# M228X.net
KiCad netlist of a schematic drawn in EAGLE
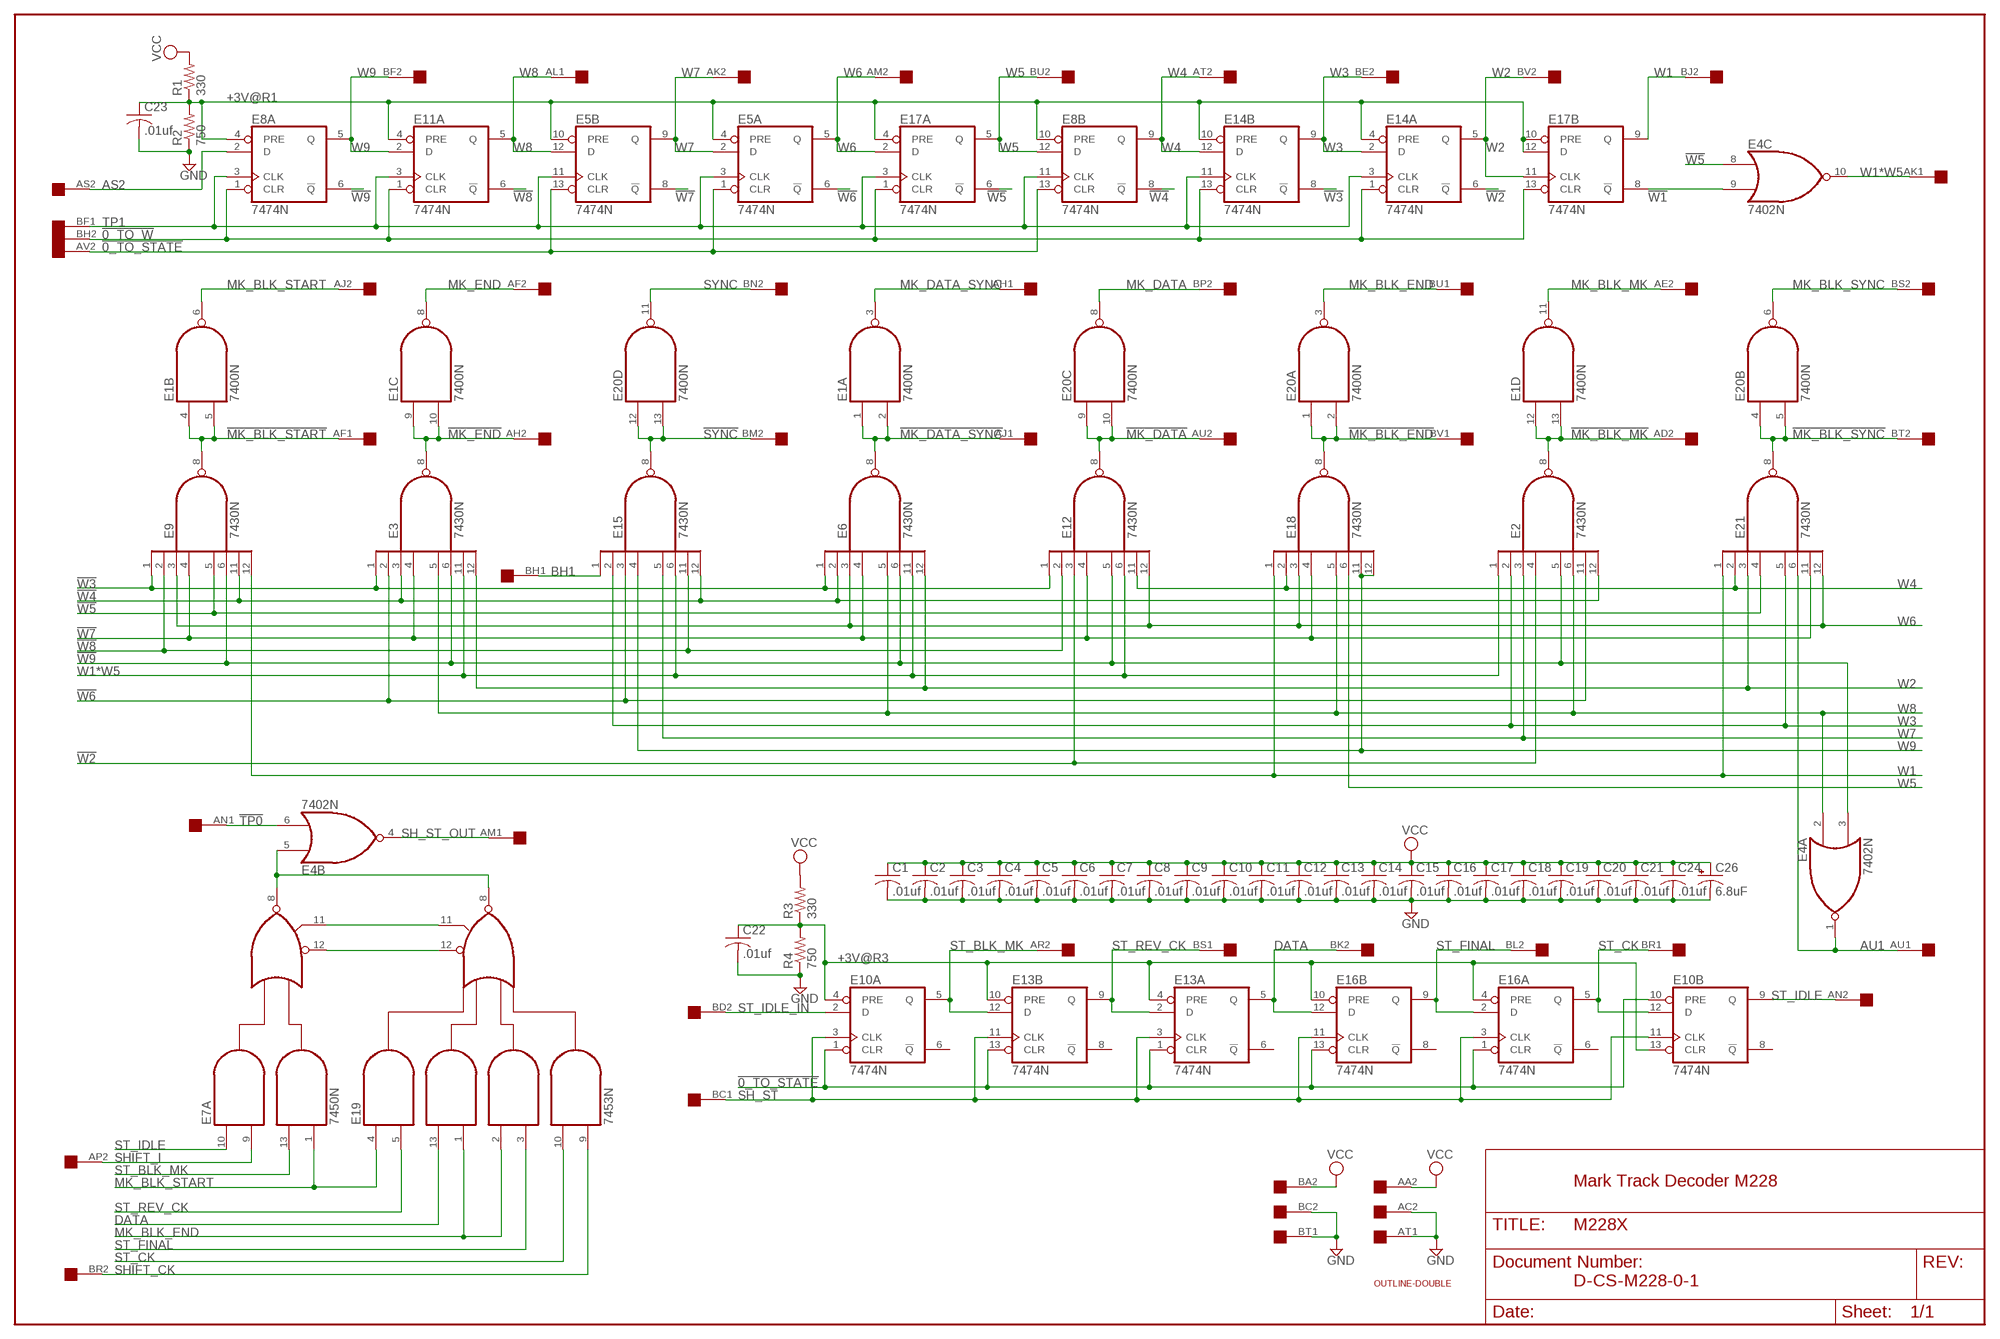
[diagram p0: schematic, sheet 1]

(export (version "E")
  (design (tool "Eeschema 10.0.6"))
  (components
    (comp (ref "C1")
      (value ".01uf")
      (footprint "eagle-import:C050-025X075")
      (libsource (lib "eagle-import") (part "C-US050-025X075"))
    )
    (comp (ref "C2")
      (value ".01uf")
      (footprint "eagle-import:C050-025X075")
      (libsource (lib "eagle-import") (part "C-US050-025X075"))
    )
    (comp (ref "C3")
      (value ".01uf")
      (footprint "eagle-import:C050-025X075")
      (libsource (lib "eagle-import") (part "C-US050-025X075"))
    )
    (comp (ref "C4")
      (value ".01uf")
      (footprint "eagle-import:C050-025X075")
      (libsource (lib "eagle-import") (part "C-US050-025X075"))
    )
    (comp (ref "C5")
      (value ".01uf")
      (footprint "eagle-import:C050-025X075")
      (libsource (lib "eagle-import") (part "C-US050-025X075"))
    )
    (comp (ref "C6")
      (value ".01uf")
      (footprint "eagle-import:C050-025X075")
      (libsource (lib "eagle-import") (part "C-US050-025X075"))
    )
    (comp (ref "C7")
      (value ".01uf")
      (footprint "eagle-import:C050-025X075")
      (libsource (lib "eagle-import") (part "C-US050-025X075"))
    )
    (comp (ref "C8")
      (value ".01uf")
      (footprint "eagle-import:C050-025X075")
      (libsource (lib "eagle-import") (part "C-US050-025X075"))
    )
    (comp (ref "C9")
      (value ".01uf")
      (footprint "eagle-import:C050-025X075")
      (libsource (lib "eagle-import") (part "C-US050-025X075"))
    )
    (comp (ref "C10")
      (value ".01uf")
      (footprint "eagle-import:C050-025X075")
      (libsource (lib "eagle-import") (part "C-US050-025X075"))
    )
    (comp (ref "C11")
      (value ".01uf")
      (footprint "eagle-import:C050-025X075")
      (libsource (lib "eagle-import") (part "C-US050-025X075"))
    )
    (comp (ref "C12")
      (value ".01uf")
      (footprint "eagle-import:C050-025X075")
      (libsource (lib "eagle-import") (part "C-US050-025X075"))
    )
    (comp (ref "C13")
      (value ".01uf")
      (footprint "eagle-import:C050-025X075")
      (libsource (lib "eagle-import") (part "C-US050-025X075"))
    )
    (comp (ref "C14")
      (value ".01uf")
      (footprint "eagle-import:C050-025X075")
      (libsource (lib "eagle-import") (part "C-US050-025X075"))
    )
    (comp (ref "C15")
      (value ".01uf")
      (footprint "eagle-import:C050-025X075")
      (libsource (lib "eagle-import") (part "C-US050-025X075"))
    )
    (comp (ref "C16")
      (value ".01uf")
      (footprint "eagle-import:C050-025X075")
      (libsource (lib "eagle-import") (part "C-US050-025X075"))
    )
    (comp (ref "C17")
      (value ".01uf")
      (footprint "eagle-import:C050-025X075")
      (libsource (lib "eagle-import") (part "C-US050-025X075"))
    )
    (comp (ref "C18")
      (value ".01uf")
      (footprint "eagle-import:C050-025X075")
      (libsource (lib "eagle-import") (part "C-US050-025X075"))
    )
    (comp (ref "C19")
      (value ".01uf")
      (footprint "eagle-import:C050-025X075")
      (libsource (lib "eagle-import") (part "C-US050-025X075"))
    )
    (comp (ref "C20")
      (value ".01uf")
      (footprint "eagle-import:C050-025X075")
      (libsource (lib "eagle-import") (part "C-US050-025X075"))
    )
    (comp (ref "C21")
      (value ".01uf")
      (footprint "eagle-import:C050-025X075")
      (libsource (lib "eagle-import") (part "C-US050-025X075"))
    )
    (comp (ref "C22")
      (value ".01uf")
      (footprint "eagle-import:C050-025X075")
      (libsource (lib "eagle-import") (part "C-US050-025X075"))
    )
    (comp (ref "C23")
      (value ".01uf")
      (footprint "eagle-import:C050-025X075")
      (libsource (lib "eagle-import") (part "C-US050-025X075"))
    )
    (comp (ref "C24")
      (value ".01uf")
      (footprint "eagle-import:C050-025X075")
      (libsource (lib "eagle-import") (part "C-US050-025X075"))
    )
    (comp (ref "C26")
      (value "6.8uF")
      (footprint "eagle-import:E22-6")
      (libsource (lib "eagle-import") (part "CPOL-USE22-6AXIAL"))
    )
    (comp (ref "E1")
      (value "7400N")
      (footprint "eagle-import:DIL14")
      (libsource (lib "eagle-import") (part "7400N"))
    )
    (comp (ref "E2")
      (value "7430N")
      (footprint "eagle-import:DIL14")
      (libsource (lib "eagle-import") (part "7430N"))
    )
    (comp (ref "E3")
      (value "7430N")
      (footprint "eagle-import:DIL14")
      (libsource (lib "eagle-import") (part "7430N"))
    )
    (comp (ref "E4")
      (value "7402N")
      (footprint "eagle-import:DIL14")
      (libsource (lib "eagle-import") (part "7402N"))
    )
    (comp (ref "E5")
      (value "7474N")
      (footprint "eagle-import:DIL14")
      (libsource (lib "eagle-import") (part "7474NS"))
    )
    (comp (ref "E6")
      (value "7430N")
      (footprint "eagle-import:DIL14")
      (libsource (lib "eagle-import") (part "7430N"))
    )
    (comp (ref "E7")
      (value "7450N")
      (footprint "eagle-import:DIL14")
      (libsource (lib "eagle-import") (part "7450N"))
    )
    (comp (ref "E8")
      (value "7474N")
      (footprint "eagle-import:DIL14")
      (libsource (lib "eagle-import") (part "7474NS"))
    )
    (comp (ref "E9")
      (value "7430N")
      (footprint "eagle-import:DIL14")
      (libsource (lib "eagle-import") (part "7430N"))
    )
    (comp (ref "E10")
      (value "7474N")
      (footprint "eagle-import:DIL14")
      (libsource (lib "eagle-import") (part "7474NS"))
    )
    (comp (ref "E11")
      (value "7474N")
      (footprint "eagle-import:DIL14")
      (libsource (lib "eagle-import") (part "7474NS"))
    )
    (comp (ref "E12")
      (value "7430N")
      (footprint "eagle-import:DIL14")
      (libsource (lib "eagle-import") (part "7430N"))
    )
    (comp (ref "E13")
      (value "7474N")
      (footprint "eagle-import:DIL14")
      (libsource (lib "eagle-import") (part "7474NS"))
    )
    (comp (ref "E14")
      (value "7474N")
      (footprint "eagle-import:DIL14")
      (libsource (lib "eagle-import") (part "7474NS"))
    )
    (comp (ref "E15")
      (value "7430N")
      (footprint "eagle-import:DIL14")
      (libsource (lib "eagle-import") (part "7430N"))
    )
    (comp (ref "E16")
      (value "7474N")
      (footprint "eagle-import:DIL14")
      (libsource (lib "eagle-import") (part "7474NS"))
    )
    (comp (ref "E17")
      (value "7474N")
      (footprint "eagle-import:DIL14")
      (libsource (lib "eagle-import") (part "7474NS"))
    )
    (comp (ref "E18")
      (value "7430N")
      (footprint "eagle-import:DIL14")
      (libsource (lib "eagle-import") (part "7430N"))
    )
    (comp (ref "E19")
      (value "7453N")
      (footprint "eagle-import:DIL14")
      (libsource (lib "eagle-import") (part "7453N"))
    )
    (comp (ref "E20")
      (value "7400N")
      (footprint "eagle-import:DIL14")
      (libsource (lib "eagle-import") (part "7400N"))
    )
    (comp (ref "E21")
      (value "7430N")
      (footprint "eagle-import:DIL14")
      (libsource (lib "eagle-import") (part "7430N"))
    )
    (comp (ref "R1")
      (value "330")
      (footprint "eagle-import:0207_10")
      (libsource (lib "eagle-import") (part "R-US_0207/10"))
    )
    (comp (ref "R2")
      (value "750")
      (footprint "eagle-import:0207_10")
      (libsource (lib "eagle-import") (part "R-US_0207/10"))
    )
    (comp (ref "R3")
      (value "330")
      (footprint "eagle-import:0207_10")
      (libsource (lib "eagle-import") (part "R-US_0207/10"))
    )
    (comp (ref "R4")
      (value "750")
      (footprint "eagle-import:0207_10")
      (libsource (lib "eagle-import") (part "R-US_0207/10"))
    )
    (comp (ref "U$1")
      (value "OUTLINE-DOUBLE")
      (footprint "eagle-import:DOUBLE")
      (libsource (lib "eagle-import") (part "OUTLINE-DOUBLE"))
    )
    (comp (ref "U$5")
      (value "DOUBLE")
      (footprint "eagle-import:EDGE-CON4")
      (libsource (lib "eagle-import") (part "DOUBLE"))
    )
  )
  (nets
    (net (code "1") (name "/+3V@R1") (class "Default")
      (node (ref "C23") (pin "1") (pinfunction "1_1") (pintype "passive"))
      (node (ref "E11") (pin "4") (pinfunction "PRE_4") (pintype "input"))
      (node (ref "E14") (pin "10") (pinfunction "PRE_10") (pintype "input"))
      (node (ref "E14") (pin "4") (pinfunction "PRE_4") (pintype "input"))
      (node (ref "E17") (pin "10") (pinfunction "PRE_10") (pintype "input"))
      (node (ref "E17") (pin "12") (pinfunction "D_12") (pintype "input"))
      (node (ref "E17") (pin "4") (pinfunction "PRE_4") (pintype "input"))
      (node (ref "E5") (pin "10") (pinfunction "PRE_10") (pintype "input"))
      (node (ref "E5") (pin "4") (pinfunction "PRE_4") (pintype "input"))
      (node (ref "E8") (pin "10") (pinfunction "PRE_10") (pintype "input"))
      (node (ref "E8") (pin "4") (pinfunction "PRE_4") (pintype "input"))
      (node (ref "R1") (pin "1") (pinfunction "1_1") (pintype "passive"))
      (node (ref "R2") (pin "2") (pinfunction "2_2") (pintype "passive"))
    )
    (net (code "2") (name "/+3V@R3") (class "Default")
      (node (ref "C22") (pin "1") (pinfunction "1_1") (pintype "passive"))
      (node (ref "E10") (pin "13") (pinfunction "CLR_13") (pintype "input"))
      (node (ref "E10") (pin "4") (pinfunction "PRE_4") (pintype "input"))
      (node (ref "E13") (pin "10") (pinfunction "PRE_10") (pintype "input"))
      (node (ref "E13") (pin "4") (pinfunction "PRE_4") (pintype "input"))
      (node (ref "E16") (pin "10") (pinfunction "PRE_10") (pintype "input"))
      (node (ref "E16") (pin "4") (pinfunction "PRE_4") (pintype "input"))
      (node (ref "R3") (pin "1") (pinfunction "1_1") (pintype "passive"))
      (node (ref "R4") (pin "2") (pinfunction "2_2") (pintype "passive"))
    )
    (net (code "3") (name "/AS2") (class "Default")
      (node (ref "E8") (pin "2") (pinfunction "D_2") (pintype "input"))
      (node (ref "U$5") (pin "AS2") (pinfunction "1_AS2") (pintype "bidirectional"))
    )
    (net (code "4") (name "/AU1") (class "Default")
      (node (ref "E21") (pin "6") (pinfunction "I5_6") (pintype "input"))
      (node (ref "E4") (pin "1") (pinfunction "O_1") (pintype "output"))
      (node (ref "U$5") (pin "AU1") (pinfunction "1_AU1") (pintype "bidirectional"))
    )
    (net (code "5") (name "/BH1") (class "Default")
      (node (ref "E15") (pin "1") (pinfunction "I0_1") (pintype "input"))
      (node (ref "U$5") (pin "BH1") (pinfunction "1_BH1") (pintype "bidirectional"))
    )
    (net (code "6") (name "/DATA") (class "Default")
      (node (ref "E13") (pin "5") (pinfunction "Q_5") (pintype "output"))
      (node (ref "E16") (pin "12") (pinfunction "D_12") (pintype "input"))
      (node (ref "E19") (pin "13") (pinfunction "I3_13") (pintype "input"))
      (node (ref "U$5") (pin "BK2") (pinfunction "1_BK2") (pintype "bidirectional"))
    )
    (net (code "7") (name "/MK_BLK_END") (class "Default")
      (node (ref "E19") (pin "1") (pinfunction "I4_1") (pintype "input"))
      (node (ref "E19") (pin "2") (pinfunction "I5_2") (pintype "input"))
      (node (ref "E20") (pin "3") (pinfunction "O_3") (pintype "output"))
      (node (ref "U$5") (pin "BU1") (pinfunction "1_BU1") (pintype "bidirectional"))
    )
    (net (code "8") (name "/MK_BLK_MK") (class "Default")
      (node (ref "E1") (pin "11") (pinfunction "O_11") (pintype "output"))
      (node (ref "U$5") (pin "AE2") (pinfunction "1_AE2") (pintype "bidirectional"))
    )
    (net (code "9") (name "/MK_BLK_START") (class "Default")
      (node (ref "E1") (pin "6") (pinfunction "O_6") (pintype "output"))
      (node (ref "E19") (pin "4") (pinfunction "I1_4") (pintype "input"))
      (node (ref "E7") (pin "1") (pinfunction "I4_1") (pintype "input"))
      (node (ref "U$5") (pin "AJ2") (pinfunction "1_AJ2") (pintype "bidirectional"))
    )
    (net (code "10") (name "/MK_BLK_SYNC") (class "Default")
      (node (ref "E20") (pin "6") (pinfunction "O_6") (pintype "output"))
      (node (ref "U$5") (pin "BS2") (pinfunction "1_BS2") (pintype "bidirectional"))
    )
    (net (code "11") (name "/MK_DATA") (class "Default")
      (node (ref "E20") (pin "8") (pinfunction "O_8") (pintype "output"))
      (node (ref "U$5") (pin "BP2") (pinfunction "1_BP2") (pintype "bidirectional"))
    )
    (net (code "12") (name "/MK_DATA_SYNC") (class "Default")
      (node (ref "E1") (pin "3") (pinfunction "O_3") (pintype "output"))
      (node (ref "U$5") (pin "AH1") (pinfunction "1_AH1") (pintype "bidirectional"))
    )
    (net (code "13") (name "/MK_END") (class "Default")
      (node (ref "E1") (pin "8") (pinfunction "O_8") (pintype "output"))
      (node (ref "U$5") (pin "AF2") (pinfunction "1_AF2") (pintype "bidirectional"))
    )
    (net (code "14") (name "/SHIFT_CK") (class "Default")
      (node (ref "E19") (pin "9") (pinfunction "I8_9") (pintype "input"))
      (node (ref "U$5") (pin "BR2") (pinfunction "1_BR2") (pintype "bidirectional"))
    )
    (net (code "15") (name "/SHIFT_I") (class "Default")
      (node (ref "E7") (pin "9") (pinfunction "I2_9") (pintype "input"))
      (node (ref "U$5") (pin "AP2") (pinfunction "1_AP2") (pintype "bidirectional"))
    )
    (net (code "16") (name "/SH_ST") (class "Default")
      (node (ref "E10") (pin "11") (pinfunction "CLK_11") (pintype "input"))
      (node (ref "E10") (pin "3") (pinfunction "CLK_3") (pintype "input"))
      (node (ref "E13") (pin "11") (pinfunction "CLK_11") (pintype "input"))
      (node (ref "E13") (pin "3") (pinfunction "CLK_3") (pintype "input"))
      (node (ref "E16") (pin "11") (pinfunction "CLK_11") (pintype "input"))
      (node (ref "E16") (pin "3") (pinfunction "CLK_3") (pintype "input"))
      (node (ref "U$5") (pin "BC1") (pinfunction "1_BC1") (pintype "bidirectional"))
    )
    (net (code "17") (name "/SH_ST_OUT") (class "Default")
      (node (ref "E4") (pin "4") (pinfunction "O_4") (pintype "output"))
      (node (ref "U$5") (pin "AM1") (pinfunction "1_AM1") (pintype "bidirectional"))
    )
    (net (code "18") (name "/ST_BLK_MK") (class "Default")
      (node (ref "E10") (pin "5") (pinfunction "Q_5") (pintype "output"))
      (node (ref "E13") (pin "12") (pinfunction "D_12") (pintype "input"))
      (node (ref "E7") (pin "13") (pinfunction "I3_13") (pintype "input"))
      (node (ref "U$5") (pin "AR2") (pinfunction "1_AR2") (pintype "bidirectional"))
    )
    (net (code "19") (name "/ST_CK") (class "Default")
      (node (ref "E10") (pin "12") (pinfunction "D_12") (pintype "input"))
      (node (ref "E16") (pin "5") (pinfunction "Q_5") (pintype "output"))
      (node (ref "E19") (pin "10") (pinfunction "I7_10") (pintype "input"))
      (node (ref "U$5") (pin "BR1") (pinfunction "1_BR1") (pintype "bidirectional"))
    )
    (net (code "20") (name "/ST_FINAL") (class "Default")
      (node (ref "E16") (pin "2") (pinfunction "D_2") (pintype "input"))
      (node (ref "E16") (pin "9") (pinfunction "Q_9") (pintype "output"))
      (node (ref "E19") (pin "3") (pinfunction "I6_3") (pintype "input"))
      (node (ref "U$5") (pin "BL2") (pinfunction "1_BL2") (pintype "bidirectional"))
    )
    (net (code "21") (name "/ST_IDLE") (class "Default")
      (node (ref "E10") (pin "9") (pinfunction "Q_9") (pintype "output"))
      (node (ref "E7") (pin "10") (pinfunction "I1_10") (pintype "input"))
      (node (ref "U$5") (pin "AN2") (pinfunction "1_AN2") (pintype "bidirectional"))
    )
    (net (code "22") (name "/ST_IDLE_IN") (class "Default")
      (node (ref "E10") (pin "2") (pinfunction "D_2") (pintype "input"))
      (node (ref "U$5") (pin "BD2") (pinfunction "1_BD2") (pintype "bidirectional"))
    )
    (net (code "23") (name "/ST_REV_CK") (class "Default")
      (node (ref "E13") (pin "2") (pinfunction "D_2") (pintype "input"))
      (node (ref "E13") (pin "9") (pinfunction "Q_9") (pintype "output"))
      (node (ref "E19") (pin "5") (pinfunction "I2_5") (pintype "input"))
      (node (ref "U$5") (pin "BS1") (pinfunction "1_BS1") (pintype "bidirectional"))
    )
    (net (code "24") (name "/SYNC") (class "Default")
      (node (ref "E20") (pin "11") (pinfunction "O_11") (pintype "output"))
      (node (ref "U$5") (pin "BN2") (pinfunction "1_BN2") (pintype "bidirectional"))
    )
    (net (code "25") (name "/TP1") (class "Default")
      (node (ref "E11") (pin "3") (pinfunction "CLK_3") (pintype "input"))
      (node (ref "E14") (pin "11") (pinfunction "CLK_11") (pintype "input"))
      (node (ref "E14") (pin "3") (pinfunction "CLK_3") (pintype "input"))
      (node (ref "E17") (pin "3") (pinfunction "CLK_3") (pintype "input"))
      (node (ref "E5") (pin "11") (pinfunction "CLK_11") (pintype "input"))
      (node (ref "E5") (pin "3") (pinfunction "CLK_3") (pintype "input"))
      (node (ref "E8") (pin "11") (pinfunction "CLK_11") (pintype "input"))
      (node (ref "E8") (pin "3") (pinfunction "CLK_3") (pintype "input"))
      (node (ref "U$5") (pin "BF1") (pinfunction "1_BF1") (pintype "bidirectional"))
    )
    (net (code "26") (name "/W1") (class "Default")
      (node (ref "E17") (pin "9") (pinfunction "Q_9") (pintype "output"))
      (node (ref "E18") (pin "1") (pinfunction "I0_1") (pintype "input"))
      (node (ref "E21") (pin "1") (pinfunction "I0_1") (pintype "input"))
      (node (ref "E9") (pin "12") (pinfunction "I7_12") (pintype "input"))
      (node (ref "U$5") (pin "BJ2") (pinfunction "1_BJ2") (pintype "bidirectional"))
    )
    (net (code "27") (name "/W1*W5") (class "Default")
      (node (ref "E12") (pin "6") (pinfunction "I5_6") (pintype "input"))
      (node (ref "E15") (pin "6") (pinfunction "I5_6") (pintype "input"))
      (node (ref "E2") (pin "1") (pinfunction "I0_1") (pintype "input"))
      (node (ref "E3") (pin "11") (pinfunction "I6_11") (pintype "input"))
      (node (ref "E4") (pin "10") (pinfunction "O_10") (pintype "output"))
      (node (ref "E6") (pin "11") (pinfunction "I6_11") (pintype "input"))
      (node (ref "U$5") (pin "AK1") (pinfunction "1_AK1") (pintype "bidirectional"))
    )
    (net (code "28") (name "/W2") (class "Default")
      (node (ref "E14") (pin "5") (pinfunction "Q_5") (pintype "output"))
      (node (ref "E17") (pin "11") (pinfunction "CLK_11") (pintype "input"))
      (node (ref "E21") (pin "3") (pinfunction "I2_3") (pintype "input"))
      (node (ref "E3") (pin "12") (pinfunction "I7_12") (pintype "input"))
      (node (ref "E6") (pin "12") (pinfunction "I7_12") (pintype "input"))
      (node (ref "U$5") (pin "BV2") (pinfunction "1_BV2") (pintype "bidirectional"))
    )
    (net (code "29") (name "/W3") (class "Default")
      (node (ref "E14") (pin "2") (pinfunction "D_2") (pintype "input"))
      (node (ref "E14") (pin "9") (pinfunction "Q_9") (pintype "output"))
      (node (ref "E15") (pin "2") (pinfunction "I1_2") (pintype "input"))
      (node (ref "E2") (pin "2") (pinfunction "I1_2") (pintype "input"))
      (node (ref "E21") (pin "5") (pinfunction "I4_5") (pintype "input"))
      (node (ref "U$5") (pin "BE2") (pinfunction "1_BE2") (pintype "bidirectional"))
    )
    (net (code "30") (name "/W4") (class "Default")
      (node (ref "E12") (pin "11") (pinfunction "I6_11") (pintype "input"))
      (node (ref "E14") (pin "12") (pinfunction "D_12") (pintype "input"))
      (node (ref "E18") (pin "2") (pinfunction "I1_2") (pintype "input"))
      (node (ref "E21") (pin "2") (pinfunction "I1_2") (pintype "input"))
      (node (ref "E8") (pin "9") (pinfunction "Q_9") (pintype "output"))
      (node (ref "U$5") (pin "AT2") (pinfunction "1_AT2") (pintype "bidirectional"))
    )
    (net (code "31") (name "/W5") (class "Default")
      (node (ref "E17") (pin "5") (pinfunction "Q_5") (pintype "output"))
      (node (ref "E18") (pin "6") (pinfunction "I5_6") (pintype "input"))
      (node (ref "E8") (pin "12") (pinfunction "D_12") (pintype "input"))
      (node (ref "U$5") (pin "BU2") (pinfunction "1_BU2") (pintype "bidirectional"))
    )
    (net (code "32") (name "/W6") (class "Default")
      (node (ref "E12") (pin "12") (pinfunction "I7_12") (pintype "input"))
      (node (ref "E17") (pin "2") (pinfunction "D_2") (pintype "input"))
      (node (ref "E18") (pin "3") (pinfunction "I2_3") (pintype "input"))
      (node (ref "E21") (pin "12") (pinfunction "I7_12") (pintype "input"))
      (node (ref "E5") (pin "5") (pinfunction "Q_5") (pintype "output"))
      (node (ref "E6") (pin "3") (pinfunction "I2_3") (pintype "input"))
      (node (ref "E9") (pin "3") (pinfunction "I2_3") (pintype "input"))
      (node (ref "U$5") (pin "AM2") (pinfunction "1_AM2") (pintype "bidirectional"))
    )
    (net (code "33") (name "/W7") (class "Default")
      (node (ref "E15") (pin "5") (pinfunction "I4_5") (pintype "input"))
      (node (ref "E2") (pin "3") (pinfunction "I2_3") (pintype "input"))
      (node (ref "E5") (pin "2") (pinfunction "D_2") (pintype "input"))
      (node (ref "E5") (pin "9") (pinfunction "Q_9") (pintype "output"))
      (node (ref "U$5") (pin "AK2") (pinfunction "1_AK2") (pintype "bidirectional"))
    )
    (net (code "34") (name "/W8") (class "Default")
      (node (ref "E11") (pin "5") (pinfunction "Q_5") (pintype "output"))
      (node (ref "E18") (pin "5") (pinfunction "I4_5") (pintype "input"))
      (node (ref "E2") (pin "6") (pinfunction "I5_6") (pintype "input"))
      (node (ref "E3") (pin "5") (pinfunction "I4_5") (pintype "input"))
      (node (ref "E4") (pin "2") (pinfunction "I0_2") (pintype "input"))
      (node (ref "E5") (pin "12") (pinfunction "D_12") (pintype "input"))
      (node (ref "E6") (pin "5") (pinfunction "I4_5") (pintype "input"))
      (node (ref "U$5") (pin "AL1") (pinfunction "1_AL1") (pintype "bidirectional"))
    )
    (net (code "35") (name "/W9") (class "Default")
      (node (ref "E11") (pin "2") (pinfunction "D_2") (pintype "input"))
      (node (ref "E15") (pin "4") (pinfunction "I3_4") (pintype "input"))
      (node (ref "E18") (pin "11") (pinfunction "I6_11") (pintype "input"))
      (node (ref "E18") (pin "12") (pinfunction "I7_12") (pintype "input"))
      (node (ref "E8") (pin "5") (pinfunction "Q_5") (pintype "output"))
      (node (ref "U$5") (pin "BF2") (pinfunction "1_BF2") (pintype "bidirectional"))
    )
    (net (code "36") (name "/~{0_TO_STATE}") (class "Default")
      (node (ref "E10") (pin "1") (pinfunction "CLR_1") (pintype "input"))
      (node (ref "E10") (pin "10") (pinfunction "PRE_10") (pintype "input"))
      (node (ref "E13") (pin "1") (pinfunction "CLR_1") (pintype "input"))
      (node (ref "E13") (pin "13") (pinfunction "CLR_13") (pintype "input"))
      (node (ref "E16") (pin "1") (pinfunction "CLR_1") (pintype "input"))
      (node (ref "E16") (pin "13") (pinfunction "CLR_13") (pintype "input"))
      (node (ref "E5") (pin "1") (pinfunction "CLR_1") (pintype "input"))
      (node (ref "E5") (pin "13") (pinfunction "CLR_13") (pintype "input"))
      (node (ref "E8") (pin "13") (pinfunction "CLR_13") (pintype "input"))
      (node (ref "U$5") (pin "AV2") (pinfunction "1_AV2") (pintype "bidirectional"))
    )
    (net (code "37") (name "/~{0_TO_W}") (class "Default")
      (node (ref "E11") (pin "1") (pinfunction "CLR_1") (pintype "input"))
      (node (ref "E14") (pin "1") (pinfunction "CLR_1") (pintype "input"))
      (node (ref "E14") (pin "13") (pinfunction "CLR_13") (pintype "input"))
      (node (ref "E17") (pin "1") (pinfunction "CLR_1") (pintype "input"))
      (node (ref "E17") (pin "13") (pinfunction "CLR_13") (pintype "input"))
      (node (ref "E8") (pin "1") (pinfunction "CLR_1") (pintype "input"))
      (node (ref "U$5") (pin "BH2") (pinfunction "1_BH2") (pintype "bidirectional"))
    )
    (net (code "38") (name "/~{MK_BLK_END}") (class "Default")
      (node (ref "E18") (pin "8") (pinfunction "O_8") (pintype "output"))
      (node (ref "E20") (pin "1") (pinfunction "I0_1") (pintype "input"))
      (node (ref "E20") (pin "2") (pinfunction "I1_2") (pintype "input"))
      (node (ref "U$5") (pin "BV1") (pinfunction "1_BV1") (pintype "bidirectional"))
    )
    (net (code "39") (name "/~{MK_BLK_MK}") (class "Default")
      (node (ref "E1") (pin "12") (pinfunction "I0_12") (pintype "input"))
      (node (ref "E1") (pin "13") (pinfunction "I1_13") (pintype "input"))
      (node (ref "E2") (pin "8") (pinfunction "O_8") (pintype "output"))
      (node (ref "U$5") (pin "AD2") (pinfunction "1_AD2") (pintype "bidirectional"))
    )
    (net (code "40") (name "/~{MK_BLK_START}") (class "Default")
      (node (ref "E1") (pin "4") (pinfunction "I0_4") (pintype "input"))
      (node (ref "E1") (pin "5") (pinfunction "I1_5") (pintype "input"))
      (node (ref "E9") (pin "8") (pinfunction "O_8") (pintype "output"))
      (node (ref "U$5") (pin "AF1") (pinfunction "1_AF1") (pintype "bidirectional"))
    )
    (net (code "41") (name "/~{MK_BLK_SYNC}") (class "Default")
      (node (ref "E20") (pin "4") (pinfunction "I0_4") (pintype "input"))
      (node (ref "E20") (pin "5") (pinfunction "I1_5") (pintype "input"))
      (node (ref "E21") (pin "8") (pinfunction "O_8") (pintype "output"))
      (node (ref "U$5") (pin "BT2") (pinfunction "1_BT2") (pintype "bidirectional"))
    )
    (net (code "42") (name "/~{MK_DATA_SYNC}") (class "Default")
      (node (ref "E1") (pin "1") (pinfunction "I0_1") (pintype "input"))
      (node (ref "E1") (pin "2") (pinfunction "I1_2") (pintype "input"))
      (node (ref "E6") (pin "8") (pinfunction "O_8") (pintype "output"))
      (node (ref "U$5") (pin "AJ1") (pinfunction "1_AJ1") (pintype "bidirectional"))
    )
    (net (code "43") (name "/~{MK_DATA}") (class "Default")
      (node (ref "E12") (pin "8") (pinfunction "O_8") (pintype "output"))
      (node (ref "E20") (pin "10") (pinfunction "I1_10") (pintype "input"))
      (node (ref "E20") (pin "9") (pinfunction "I0_9") (pintype "input"))
      (node (ref "U$5") (pin "AU2") (pinfunction "1_AU2") (pintype "bidirectional"))
    )
    (net (code "44") (name "/~{MK_END}") (class "Default")
      (node (ref "E1") (pin "10") (pinfunction "I1_10") (pintype "input"))
      (node (ref "E1") (pin "9") (pinfunction "I0_9") (pintype "input"))
      (node (ref "E3") (pin "8") (pinfunction "O_8") (pintype "output"))
      (node (ref "U$5") (pin "AH2") (pinfunction "1_AH2") (pintype "bidirectional"))
    )
    (net (code "45") (name "/~{SYNC}") (class "Default")
      (node (ref "E15") (pin "8") (pinfunction "O_8") (pintype "output"))
      (node (ref "E20") (pin "12") (pinfunction "I0_12") (pintype "input"))
      (node (ref "E20") (pin "13") (pinfunction "I1_13") (pintype "input"))
      (node (ref "U$5") (pin "BM2") (pinfunction "1_BM2") (pintype "bidirectional"))
    )
    (net (code "46") (name "/~{TP0}") (class "Default")
      (node (ref "E4") (pin "6") (pinfunction "I1_6") (pintype "input"))
      (node (ref "U$5") (pin "AN1") (pinfunction "1_AN1") (pintype "bidirectional"))
    )
    (net (code "47") (name "/~{W1}") (class "Default")
      (node (ref "E17") (pin "8") (pinfunction "~{Q}_8") (pintype "output"))
      (node (ref "E4") (pin "9") (pinfunction "I1_9") (pintype "input"))
    )
    (net (code "48") (name "/~{W2}") (class "Default")
      (node (ref "E12") (pin "3") (pinfunction "I2_3") (pintype "input"))
      (node (ref "E14") (pin "6") (pinfunction "~{Q}_6") (pintype "output"))
      (node (ref "E2") (pin "4") (pinfunction "I3_4") (pintype "input"))
    )
    (net (code "49") (name "/~{W3}") (class "Default")
      (node (ref "E12") (pin "1") (pinfunction "I0_1") (pintype "input"))
      (node (ref "E14") (pin "8") (pinfunction "~{Q}_8") (pintype "output"))
      (node (ref "E3") (pin "1") (pinfunction "I0_1") (pintype "input"))
      (node (ref "E6") (pin "1") (pinfunction "I0_1") (pintype "input"))
      (node (ref "E9") (pin "1") (pinfunction "I0_1") (pintype "input"))
    )
    (net (code "50") (name "/~{W4}") (class "Default")
      (node (ref "E15") (pin "12") (pinfunction "I7_12") (pintype "input"))
      (node (ref "E2") (pin "12") (pinfunction "I7_12") (pintype "input"))
      (node (ref "E3") (pin "3") (pinfunction "I2_3") (pintype "input"))
      (node (ref "E6") (pin "2") (pinfunction "I1_2") (pintype "input"))
      (node (ref "E8") (pin "8") (pinfunction "~{Q}_8") (pintype "output"))
      (node (ref "E9") (pin "11") (pinfunction "I6_11") (pintype "input"))
    )
    (net (code "51") (name "/~{W5}") (class "Default")
      (node (ref "E17") (pin "6") (pinfunction "~{Q}_6") (pintype "output"))
      (node (ref "E21") (pin "4") (pinfunction "I3_4") (pintype "input"))
      (node (ref "E4") (pin "8") (pinfunction "I0_8") (pintype "input"))
      (node (ref "E9") (pin "5") (pinfunction "I4_5") (pintype "input"))
    )
    (net (code "52") (name "/~{W6}") (class "Default")
      (node (ref "E15") (pin "3") (pinfunction "I2_3") (pintype "input"))
      (node (ref "E2") (pin "11") (pinfunction "I6_11") (pintype "input"))
      (node (ref "E3") (pin "2") (pinfunction "I1_2") (pintype "input"))
      (node (ref "E5") (pin "6") (pinfunction "~{Q}_6") (pintype "output"))
    )
    (net (code "53") (name "/~{W7}") (class "Default")
      (node (ref "E12") (pin "4") (pinfunction "I3_4") (pintype "input"))
      (node (ref "E18") (pin "4") (pinfunction "I3_4") (pintype "input"))
      (node (ref "E21") (pin "11") (pinfunction "I6_11") (pintype "input"))
      (node (ref "E3") (pin "4") (pinfunction "I3_4") (pintype "input"))
      (node (ref "E5") (pin "8") (pinfunction "~{Q}_8") (pintype "output"))
      (node (ref "E6") (pin "4") (pinfunction "I3_4") (pintype "input"))
      (node (ref "E9") (pin "4") (pinfunction "I3_4") (pintype "input"))
    )
    (net (code "54") (name "/~{W8}") (class "Default")
      (node (ref "E11") (pin "6") (pinfunction "~{Q}_6") (pintype "output"))
      (node (ref "E12") (pin "2") (pinfunction "I1_2") (pintype "input"))
      (node (ref "E15") (pin "11") (pinfunction "I6_11") (pintype "input"))
      (node (ref "E9") (pin "2") (pinfunction "I1_2") (pintype "input"))
    )
    (net (code "55") (name "/~{W9}") (class "Default")
      (node (ref "E12") (pin "5") (pinfunction "I4_5") (pintype "input"))
      (node (ref "E2") (pin "5") (pinfunction "I4_5") (pintype "input"))
      (node (ref "E3") (pin "6") (pinfunction "I5_6") (pintype "input"))
      (node (ref "E4") (pin "3") (pinfunction "I1_3") (pintype "input"))
      (node (ref "E6") (pin "6") (pinfunction "I5_6") (pintype "input"))
      (node (ref "E8") (pin "6") (pinfunction "~{Q}_6") (pintype "output"))
      (node (ref "E9") (pin "6") (pinfunction "I5_6") (pintype "input"))
    )
    (net (code "56") (name "GND") (class "Default")
      (node (ref "C1") (pin "2") (pinfunction "2_2") (pintype "passive"))
      (node (ref "C10") (pin "2") (pinfunction "2_2") (pintype "passive"))
      (node (ref "C11") (pin "2") (pinfunction "2_2") (pintype "passive"))
      (node (ref "C12") (pin "2") (pinfunction "2_2") (pintype "passive"))
      (node (ref "C13") (pin "2") (pinfunction "2_2") (pintype "passive"))
      (node (ref "C14") (pin "2") (pinfunction "2_2") (pintype "passive"))
      (node (ref "C15") (pin "2") (pinfunction "2_2") (pintype "passive"))
      (node (ref "C16") (pin "2") (pinfunction "2_2") (pintype "passive"))
      (node (ref "C17") (pin "2") (pinfunction "2_2") (pintype "passive"))
      (node (ref "C18") (pin "2") (pinfunction "2_2") (pintype "passive"))
      (node (ref "C19") (pin "2") (pinfunction "2_2") (pintype "passive"))
      (node (ref "C2") (pin "2") (pinfunction "2_2") (pintype "passive"))
      (node (ref "C20") (pin "2") (pinfunction "2_2") (pintype "passive"))
      (node (ref "C21") (pin "2") (pinfunction "2_2") (pintype "passive"))
      (node (ref "C22") (pin "2") (pinfunction "2_2") (pintype "passive"))
      (node (ref "C23") (pin "2") (pinfunction "2_2") (pintype "passive"))
      (node (ref "C24") (pin "2") (pinfunction "2_2") (pintype "passive"))
      (node (ref "C26") (pin "-") (pinfunction "-_-") (pintype "passive"))
      (node (ref "C3") (pin "2") (pinfunction "2_2") (pintype "passive"))
      (node (ref "C4") (pin "2") (pinfunction "2_2") (pintype "passive"))
      (node (ref "C5") (pin "2") (pinfunction "2_2") (pintype "passive"))
      (node (ref "C6") (pin "2") (pinfunction "2_2") (pintype "passive"))
      (node (ref "C7") (pin "2") (pinfunction "2_2") (pintype "passive"))
      (node (ref "C8") (pin "2") (pinfunction "2_2") (pintype "passive"))
      (node (ref "C9") (pin "2") (pinfunction "2_2") (pintype "passive"))
      (node (ref "R2") (pin "1") (pinfunction "1_1") (pintype "passive"))
      (node (ref "R4") (pin "1") (pinfunction "1_1") (pintype "passive"))
      (node (ref "U$5") (pin "AC2") (pinfunction "1_AC2") (pintype "bidirectional"))
      (node (ref "U$5") (pin "AT1") (pinfunction "1_AT1") (pintype "bidirectional"))
      (node (ref "U$5") (pin "BC2") (pinfunction "1_BC2") (pintype "bidirectional"))
      (node (ref "U$5") (pin "BT1") (pinfunction "1_BT1") (pintype "bidirectional"))
    )
    (net (code "57") (name "Net-(E19A-I9)") (class "Default")
      (node (ref "E19") (pin "12") (pinfunction "I9_12") (pintype "passive"))
      (node (ref "E7") (pin "12") (pinfunction "I5_12") (pintype "passive"))
    )
    (net (code "58") (name "Net-(E19A-I10)") (class "Default")
      (node (ref "E19") (pin "11") (pinfunction "I10_11") (pintype "passive"))
      (node (ref "E7") (pin "11") (pinfunction "I6_11") (pintype "passive"))
    )
    (net (code "59") (name "Net-(E19A-O)") (class "Default")
      (node (ref "E19") (pin "8") (pinfunction "O_8") (pintype "output"))
      (node (ref "E4") (pin "5") (pinfunction "I0_5") (pintype "input"))
      (node (ref "E7") (pin "8") (pinfunction "O_8") (pintype "output"))
    )
    (net (code "60") (name "VCC") (class "Default")
      (node (ref "C1") (pin "1") (pinfunction "1_1") (pintype "passive"))
      (node (ref "C10") (pin "1") (pinfunction "1_1") (pintype "passive"))
      (node (ref "C11") (pin "1") (pinfunction "1_1") (pintype "passive"))
      (node (ref "C12") (pin "1") (pinfunction "1_1") (pintype "passive"))
      (node (ref "C13") (pin "1") (pinfunction "1_1") (pintype "passive"))
      (node (ref "C14") (pin "1") (pinfunction "1_1") (pintype "passive"))
      (node (ref "C15") (pin "1") (pinfunction "1_1") (pintype "passive"))
      (node (ref "C16") (pin "1") (pinfunction "1_1") (pintype "passive"))
      (node (ref "C17") (pin "1") (pinfunction "1_1") (pintype "passive"))
      (node (ref "C18") (pin "1") (pinfunction "1_1") (pintype "passive"))
      (node (ref "C19") (pin "1") (pinfunction "1_1") (pintype "passive"))
      (node (ref "C2") (pin "1") (pinfunction "1_1") (pintype "passive"))
      (node (ref "C20") (pin "1") (pinfunction "1_1") (pintype "passive"))
      (node (ref "C21") (pin "1") (pinfunction "1_1") (pintype "passive"))
      (node (ref "C24") (pin "1") (pinfunction "1_1") (pintype "passive"))
      (node (ref "C26") (pin "+") (pinfunction "+_+") (pintype "passive"))
      (node (ref "C3") (pin "1") (pinfunction "1_1") (pintype "passive"))
      (node (ref "C4") (pin "1") (pinfunction "1_1") (pintype "passive"))
      (node (ref "C5") (pin "1") (pinfunction "1_1") (pintype "passive"))
      (node (ref "C6") (pin "1") (pinfunction "1_1") (pintype "passive"))
      (node (ref "C7") (pin "1") (pinfunction "1_1") (pintype "passive"))
      (node (ref "C8") (pin "1") (pinfunction "1_1") (pintype "passive"))
      (node (ref "C9") (pin "1") (pinfunction "1_1") (pintype "passive"))
      (node (ref "R1") (pin "2") (pinfunction "2_2") (pintype "passive"))
      (node (ref "R3") (pin "2") (pinfunction "2_2") (pintype "passive"))
      (node (ref "U$5") (pin "AA2") (pinfunction "1_AA2") (pintype "bidirectional"))
      (node (ref "U$5") (pin "BA2") (pinfunction "1_BA2") (pintype "bidirectional"))
    )
    (net (code "61") (name "unconnected-(E10A-~{Q}-Pad6)") (class "Default")
      (node (ref "E10") (pin "6") (pinfunction "~{Q}_6") (pintype "output"))
    )
    (net (code "62") (name "unconnected-(E10B-~{Q}-Pad8)") (class "Default")
      (node (ref "E10") (pin "8") (pinfunction "~{Q}_8") (pintype "output"))
    )
    (net (code "63") (name "unconnected-(E13A-~{Q}-Pad6)") (class "Default")
      (node (ref "E13") (pin "6") (pinfunction "~{Q}_6") (pintype "output"))
    )
    (net (code "64") (name "unconnected-(E13B-~{Q}-Pad8)") (class "Default")
      (node (ref "E13") (pin "8") (pinfunction "~{Q}_8") (pintype "output"))
    )
    (net (code "65") (name "unconnected-(E16A-~{Q}-Pad6)") (class "Default")
      (node (ref "E16") (pin "6") (pinfunction "~{Q}_6") (pintype "output"))
    )
    (net (code "66") (name "unconnected-(E16B-~{Q}-Pad8)") (class "Default")
      (node (ref "E16") (pin "8") (pinfunction "~{Q}_8") (pintype "output"))
    )
  )
)
